# HDMI.net
KiCad netlist of a schematic drawn in Altium Designer
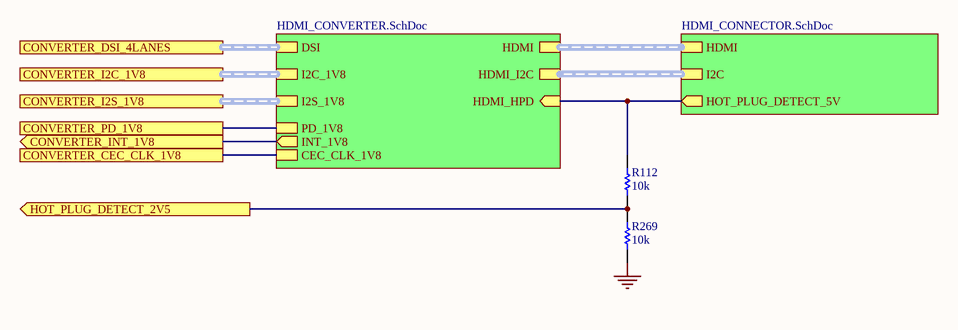
[diagram p0: HDMI.SchDoc]

(export (version "E")
  (design (tool "Eeschema 10.0.6"))
  (components
    (comp (ref "R112")
      (value "10k")
      (footprint "RES-0201")
      (description "RES CHIP 0201 10k 1% 1/20W")
      (fields (field (name "POWER") "50mW") (field (name "TOLERANCE") "1%"))
      (libsource (lib "Clean") (part "RES"))
    )
    (comp (ref "R269")
      (value "10k")
      (footprint "RES-0201")
      (description "RES CHIP 0201 10k 1% 1/20W")
      (fields (field (name "POWER") "50mW") (field (name "TOLERANCE") "1%"))
      (libsource (lib "Clean") (part "RES"))
    )
  )
  (nets
    (net (code "12") (name "/HOT_PLUG_DETECT_2V5") (class "Default")
      (node (ref "R112") (pin "1") (pinfunction "1_1") (pintype "passive"))
      (node (ref "R269") (pin "2") (pinfunction "2_2") (pintype "passive"))
    )
    (net (code "13") (name "/HOT_PLUG_DETECT_5V") (class "Default")
      (node (ref "R112") (pin "2") (pinfunction "2_2") (pintype "passive"))
    )
    (net (code "14") (name "GND") (class "Default")
      (node (ref "R269") (pin "1") (pinfunction "1_1") (pintype "passive"))
    )
  )
)
